# ledblinker.net
KiCad netlist of a schematic drawn in EAGLE
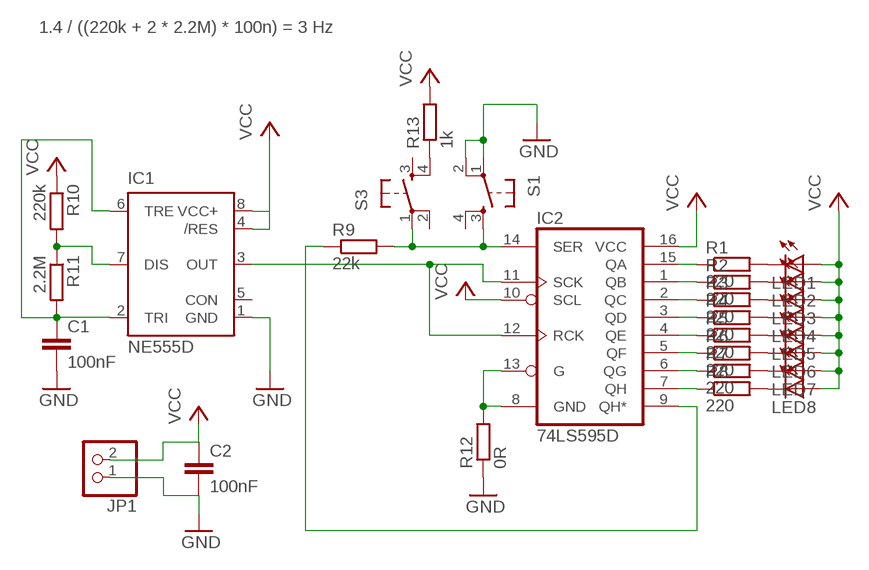
[diagram p0: schematic, sheet 1]

(export (version "E")
  (design (tool "Eeschema 10.0.6"))
  (components
    (comp (ref "C1")
      (value "100nF")
      (footprint "eagle-import:C1206")
      (libsource (lib "eagle-import") (part "C-EUC1206"))
    )
    (comp (ref "C2")
      (value "100nF")
      (footprint "eagle-import:C1206")
      (libsource (lib "eagle-import") (part "C-EUC1206"))
    )
    (comp (ref "IC1")
      (value "NE555D")
      (footprint "eagle-import:SO08")
      (libsource (lib "eagle-import") (part "NE555D"))
    )
    (comp (ref "IC2")
      (value "74LS595D")
      (footprint "eagle-import:SO16")
      (libsource (lib "eagle-import") (part "74595DLS"))
    )
    (comp (ref "JP1")
      (value "PINHD-1X2/90")
      (footprint "eagle-import:1X02_90")
      (libsource (lib "eagle-import") (part "PINHD-1X2/90"))
    )
    (comp (ref "LED1")
      (value "LEDCHIPLED_1206")
      (footprint "eagle-import:CHIPLED_1206")
      (libsource (lib "eagle-import") (part "LEDCHIPLED_1206"))
    )
    (comp (ref "LED2")
      (value "LEDCHIPLED_1206")
      (footprint "eagle-import:CHIPLED_1206")
      (libsource (lib "eagle-import") (part "LEDCHIPLED_1206"))
    )
    (comp (ref "LED3")
      (value "LEDCHIPLED_1206")
      (footprint "eagle-import:CHIPLED_1206")
      (libsource (lib "eagle-import") (part "LEDCHIPLED_1206"))
    )
    (comp (ref "LED4")
      (value "LEDCHIPLED_1206")
      (footprint "eagle-import:CHIPLED_1206")
      (libsource (lib "eagle-import") (part "LEDCHIPLED_1206"))
    )
    (comp (ref "LED5")
      (value "LEDCHIPLED_1206")
      (footprint "eagle-import:CHIPLED_1206")
      (libsource (lib "eagle-import") (part "LEDCHIPLED_1206"))
    )
    (comp (ref "LED6")
      (value "LEDCHIPLED_1206")
      (footprint "eagle-import:CHIPLED_1206")
      (libsource (lib "eagle-import") (part "LEDCHIPLED_1206"))
    )
    (comp (ref "LED7")
      (value "LEDCHIPLED_1206")
      (footprint "eagle-import:CHIPLED_1206")
      (libsource (lib "eagle-import") (part "LEDCHIPLED_1206"))
    )
    (comp (ref "LED8")
      (value "LEDCHIPLED_1206")
      (footprint "eagle-import:CHIPLED_1206")
      (libsource (lib "eagle-import") (part "LEDCHIPLED_1206"))
    )
    (comp (ref "R1")
      (value "220")
      (footprint "eagle-import:M1206")
      (libsource (lib "eagle-import") (part "R-EU_M1206"))
    )
    (comp (ref "R2")
      (value "220")
      (footprint "eagle-import:M1206")
      (libsource (lib "eagle-import") (part "R-EU_M1206"))
    )
    (comp (ref "R3")
      (value "220")
      (footprint "eagle-import:M1206")
      (libsource (lib "eagle-import") (part "R-EU_M1206"))
    )
    (comp (ref "R4")
      (value "220")
      (footprint "eagle-import:M1206")
      (libsource (lib "eagle-import") (part "R-EU_M1206"))
    )
    (comp (ref "R5")
      (value "220")
      (footprint "eagle-import:M1206")
      (libsource (lib "eagle-import") (part "R-EU_M1206"))
    )
    (comp (ref "R6")
      (value "220")
      (footprint "eagle-import:M1206")
      (libsource (lib "eagle-import") (part "R-EU_M1206"))
    )
    (comp (ref "R7")
      (value "220")
      (footprint "eagle-import:M1206")
      (libsource (lib "eagle-import") (part "R-EU_M1206"))
    )
    (comp (ref "R8")
      (value "220")
      (footprint "eagle-import:M1206")
      (libsource (lib "eagle-import") (part "R-EU_M1206"))
    )
    (comp (ref "R9")
      (value "22k")
      (footprint "eagle-import:M1206")
      (libsource (lib "eagle-import") (part "R-EU_M1206"))
    )
    (comp (ref "R10")
      (value "220k")
      (footprint "eagle-import:M1206")
      (libsource (lib "eagle-import") (part "R-EU_M1206"))
    )
    (comp (ref "R11")
      (value "2.2M")
      (footprint "eagle-import:M1206")
      (libsource (lib "eagle-import") (part "R-EU_M1206"))
    )
    (comp (ref "R12")
      (value "0R")
      (footprint "eagle-import:R1206")
      (libsource (lib "eagle-import") (part "R-EU_R1206"))
    )
    (comp (ref "R13")
      (value "1k")
      (footprint "eagle-import:M1206")
      (libsource (lib "eagle-import") (part "R-EU_M1206"))
    )
    (comp (ref "S1")
      (value "TAC_SWITCHSMD2")
      (footprint "eagle-import:TACTILE_SWITCH_TALL")
      (libsource (lib "eagle-import") (part "TAC_SWITCHSMD2"))
    )
    (comp (ref "S3")
      (value "TAC_SWITCHSMD2")
      (footprint "eagle-import:TACTILE_SWITCH_TALL")
      (libsource (lib "eagle-import") (part "TAC_SWITCHSMD2"))
    )
  )
  (nets
    (net (code "1") (name "GND") (class "Default")
      (node (ref "C1") (pin "2") (pinfunction "2_2") (pintype "passive"))
      (node (ref "C2") (pin "2") (pinfunction "2_2") (pintype "passive"))
      (node (ref "IC1") (pin "1") (pinfunction "GND_1") (pintype "power_in"))
      (node (ref "JP1") (pin "1") (pinfunction "1_1") (pintype "passive"))
      (node (ref "R12") (pin "1") (pinfunction "1_1") (pintype "passive"))
      (node (ref "S1") (pin "1") (pinfunction "1_1") (pintype "passive"))
      (node (ref "S1") (pin "2") (pinfunction "2_2") (pintype "passive"))
    )
    (net (code "2") (name "Net-(IC1-DIS)") (class "Default")
      (node (ref "IC1") (pin "7") (pinfunction "DIS_7") (pintype "input"))
      (node (ref "R10") (pin "2") (pinfunction "2_2") (pintype "passive"))
      (node (ref "R11") (pin "1") (pinfunction "1_1") (pintype "passive"))
    )
    (net (code "3") (name "Net-(IC1-OUT)") (class "Default")
      (node (ref "IC1") (pin "3") (pinfunction "OUT_3") (pintype "output"))
      (node (ref "IC2") (pin "11") (pinfunction "SCK_11") (pintype "input"))
      (node (ref "IC2") (pin "12") (pinfunction "RCK_12") (pintype "input"))
    )
    (net (code "4") (name "Net-(IC1-TRE)") (class "Default")
      (node (ref "C1") (pin "1") (pinfunction "1_1") (pintype "passive"))
      (node (ref "IC1") (pin "2") (pinfunction "TRI_2") (pintype "input"))
      (node (ref "IC1") (pin "6") (pinfunction "TRE_6") (pintype "input"))
      (node (ref "R11") (pin "2") (pinfunction "2_2") (pintype "passive"))
    )
    (net (code "5") (name "Net-(IC2-G)") (class "Default")
      (node (ref "IC2") (pin "13") (pinfunction "G_13") (pintype "input"))
      (node (ref "IC2") (pin "8") (pinfunction "GND_8") (pintype "power_in"))
      (node (ref "R12") (pin "2") (pinfunction "2_2") (pintype "passive"))
    )
    (net (code "6") (name "Net-(IC2-QA)") (class "Default")
      (node (ref "IC2") (pin "15") (pinfunction "QA_15") (pintype "tri_state"))
      (node (ref "R1") (pin "1") (pinfunction "1_1") (pintype "passive"))
    )
    (net (code "7") (name "Net-(IC2-QB)") (class "Default")
      (node (ref "IC2") (pin "1") (pinfunction "QB_1") (pintype "tri_state"))
      (node (ref "R2") (pin "1") (pinfunction "1_1") (pintype "passive"))
    )
    (net (code "8") (name "Net-(IC2-QC)") (class "Default")
      (node (ref "IC2") (pin "2") (pinfunction "QC_2") (pintype "tri_state"))
      (node (ref "R3") (pin "1") (pinfunction "1_1") (pintype "passive"))
    )
    (net (code "9") (name "Net-(IC2-QD)") (class "Default")
      (node (ref "IC2") (pin "3") (pinfunction "QD_3") (pintype "tri_state"))
      (node (ref "R4") (pin "1") (pinfunction "1_1") (pintype "passive"))
    )
    (net (code "10") (name "Net-(IC2-QE)") (class "Default")
      (node (ref "IC2") (pin "4") (pinfunction "QE_4") (pintype "tri_state"))
      (node (ref "R5") (pin "1") (pinfunction "1_1") (pintype "passive"))
    )
    (net (code "11") (name "Net-(IC2-QF)") (class "Default")
      (node (ref "IC2") (pin "5") (pinfunction "QF_5") (pintype "tri_state"))
      (node (ref "R6") (pin "1") (pinfunction "1_1") (pintype "passive"))
    )
    (net (code "12") (name "Net-(IC2-QG)") (class "Default")
      (node (ref "IC2") (pin "6") (pinfunction "QG_6") (pintype "tri_state"))
      (node (ref "R7") (pin "1") (pinfunction "1_1") (pintype "passive"))
    )
    (net (code "13") (name "Net-(IC2-QH)") (class "Default")
      (node (ref "IC2") (pin "7") (pinfunction "QH_7") (pintype "tri_state"))
      (node (ref "R8") (pin "1") (pinfunction "1_1") (pintype "passive"))
    )
    (net (code "14") (name "Net-(IC2-QH*)") (class "Default")
      (node (ref "IC2") (pin "9") (pinfunction "QH*_9") (pintype "tri_state"))
      (node (ref "R9") (pin "1") (pinfunction "1_1") (pintype "passive"))
    )
    (net (code "15") (name "Net-(IC2-SER)") (class "Default")
      (node (ref "IC2") (pin "14") (pinfunction "SER_14") (pintype "input"))
      (node (ref "R9") (pin "2") (pinfunction "2_2") (pintype "passive"))
      (node (ref "S1") (pin "3") (pinfunction "3_3") (pintype "passive"))
      (node (ref "S3") (pin "1") (pinfunction "1_1") (pintype "passive"))
    )
    (net (code "16") (name "Net-(LED1-PadC)") (class "Default")
      (node (ref "LED1") (pin "C") (pinfunction "C_C") (pintype "passive"))
      (node (ref "R1") (pin "2") (pinfunction "2_2") (pintype "passive"))
    )
    (net (code "17") (name "Net-(LED2-PadC)") (class "Default")
      (node (ref "LED2") (pin "C") (pinfunction "C_C") (pintype "passive"))
      (node (ref "R2") (pin "2") (pinfunction "2_2") (pintype "passive"))
    )
    (net (code "18") (name "Net-(LED3-PadC)") (class "Default")
      (node (ref "LED3") (pin "C") (pinfunction "C_C") (pintype "passive"))
      (node (ref "R3") (pin "2") (pinfunction "2_2") (pintype "passive"))
    )
    (net (code "19") (name "Net-(LED4-PadC)") (class "Default")
      (node (ref "LED4") (pin "C") (pinfunction "C_C") (pintype "passive"))
      (node (ref "R4") (pin "2") (pinfunction "2_2") (pintype "passive"))
    )
    (net (code "20") (name "Net-(LED5-PadC)") (class "Default")
      (node (ref "LED5") (pin "C") (pinfunction "C_C") (pintype "passive"))
      (node (ref "R5") (pin "2") (pinfunction "2_2") (pintype "passive"))
    )
    (net (code "21") (name "Net-(LED6-PadC)") (class "Default")
      (node (ref "LED6") (pin "C") (pinfunction "C_C") (pintype "passive"))
      (node (ref "R6") (pin "2") (pinfunction "2_2") (pintype "passive"))
    )
    (net (code "22") (name "Net-(LED7-PadC)") (class "Default")
      (node (ref "LED7") (pin "C") (pinfunction "C_C") (pintype "passive"))
      (node (ref "R7") (pin "2") (pinfunction "2_2") (pintype "passive"))
    )
    (net (code "23") (name "Net-(LED8-PadC)") (class "Default")
      (node (ref "LED8") (pin "C") (pinfunction "C_C") (pintype "passive"))
      (node (ref "R8") (pin "2") (pinfunction "2_2") (pintype "passive"))
    )
    (net (code "24") (name "Net-(R13-Pad1)") (class "Default")
      (node (ref "R13") (pin "1") (pinfunction "1_1") (pintype "passive"))
      (node (ref "S3") (pin "4") (pinfunction "4_4") (pintype "passive"))
    )
    (net (code "25") (name "VCC") (class "Default")
      (node (ref "C2") (pin "1") (pinfunction "1_1") (pintype "passive"))
      (node (ref "IC1") (pin "4") (pinfunction "/RES_4") (pintype "input"))
      (node (ref "IC1") (pin "8") (pinfunction "VCC+_8") (pintype "power_in"))
      (node (ref "IC2") (pin "10") (pinfunction "SCL_10") (pintype "input"))
      (node (ref "IC2") (pin "16") (pinfunction "VCC_16") (pintype "power_in"))
      (node (ref "JP1") (pin "2") (pinfunction "2_2") (pintype "passive"))
      (node (ref "LED1") (pin "A") (pinfunction "A_A") (pintype "passive"))
      (node (ref "LED2") (pin "A") (pinfunction "A_A") (pintype "passive"))
      (node (ref "LED3") (pin "A") (pinfunction "A_A") (pintype "passive"))
      (node (ref "LED4") (pin "A") (pinfunction "A_A") (pintype "passive"))
      (node (ref "LED5") (pin "A") (pinfunction "A_A") (pintype "passive"))
      (node (ref "LED6") (pin "A") (pinfunction "A_A") (pintype "passive"))
      (node (ref "LED7") (pin "A") (pinfunction "A_A") (pintype "passive"))
      (node (ref "LED8") (pin "A") (pinfunction "A_A") (pintype "passive"))
      (node (ref "R10") (pin "1") (pinfunction "1_1") (pintype "passive"))
      (node (ref "R13") (pin "2") (pinfunction "2_2") (pintype "passive"))
    )
    (net (code "26") (name "unconnected-(IC1-CON-Pad5)") (class "Default")
      (node (ref "IC1") (pin "5") (pinfunction "CON_5") (pintype "input"))
    )
    (net (code "27") (name "unconnected-(S1-Pad4)") (class "Default")
      (node (ref "S1") (pin "4") (pinfunction "4_4") (pintype "passive"))
    )
    (net (code "28") (name "unconnected-(S3-Pad2)") (class "Default")
      (node (ref "S3") (pin "2") (pinfunction "2_2") (pintype "passive"))
    )
    (net (code "29") (name "unconnected-(S3-Pad3)") (class "Default")
      (node (ref "S3") (pin "3") (pinfunction "3_3") (pintype "passive"))
    )
  )
)
